# Power_Schematics.net
KiCad netlist of a schematic drawn in Altium Designer
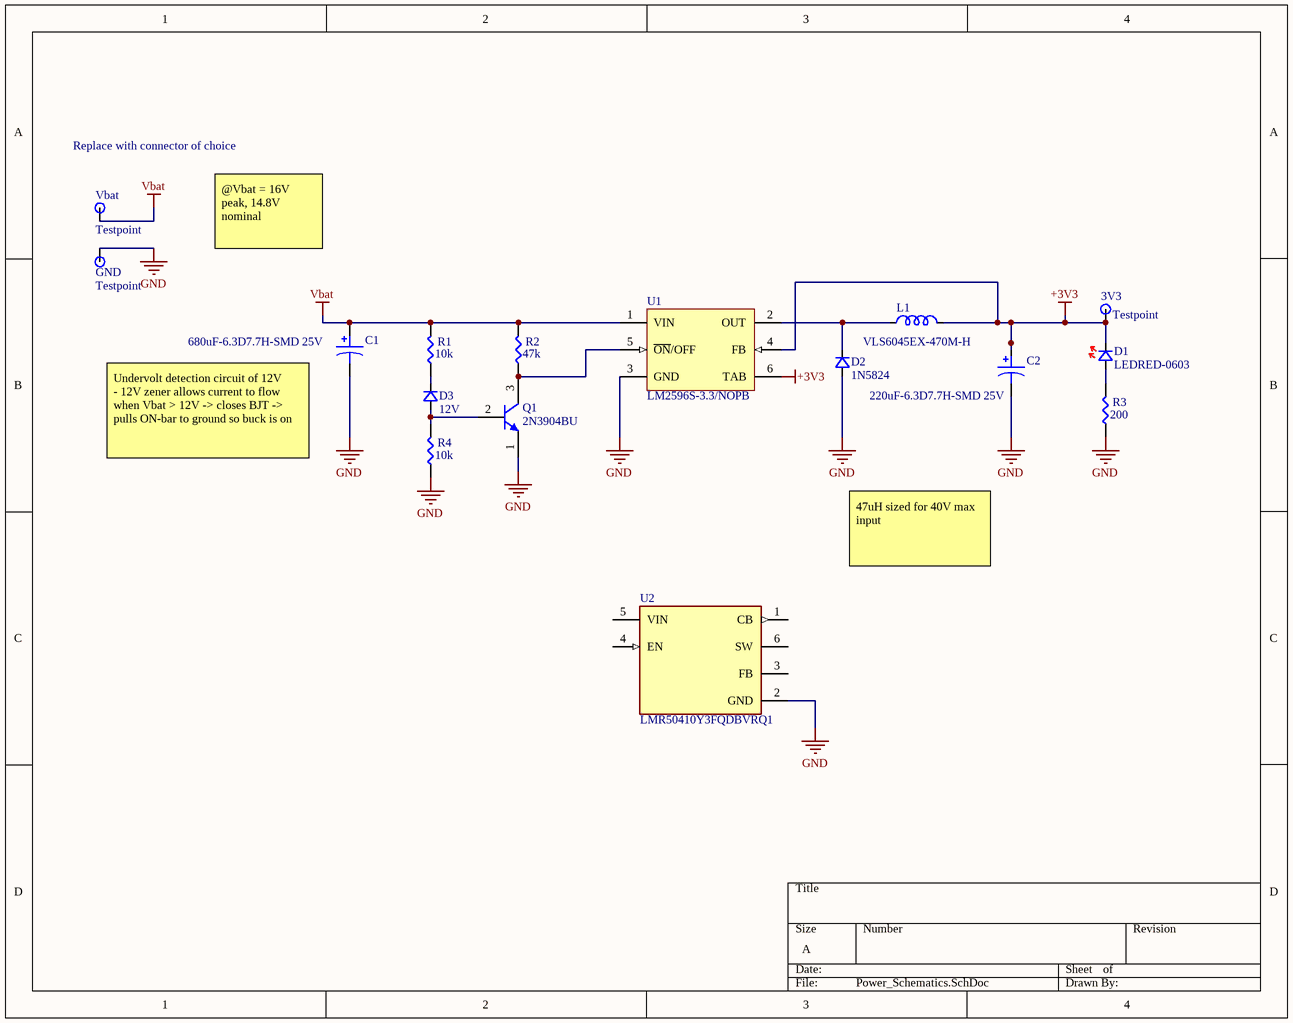
[diagram p0: Power_Schematics.SchDoc]

(export (version "E")
  (design (tool "Eeschema 10.0.6"))
  (components
    (comp (ref "3V3")
      (value "Testpoint")
      (footprint "Testpoint")
      (fields (field (name "SOURCE") "ife19_Elec_Library.SchLib"))
      (libsource (lib "Illini Formula Electric") (part "Testpoint"))
    )
    (comp (ref "C1")
      (value "680uF-6.3D7.7H-SMD 25V")
      (footprint "CAP-6.3D7.7H-SMD")
      (fields (field (name "SOURCE") "ife19_Elec_Library.SchLib"))
      (libsource (lib "Illini Formula Electric") (part "CAP-6.3D7.7H-SMD"))
    )
    (comp (ref "C2")
      (value "220uF-6.3D7.7H-SMD 25V")
      (footprint "CAP-6.3D7.7H-SMD")
      (fields (field (name "SOURCE") "ife19_Elec_Library.SchLib"))
      (libsource (lib "Illini Formula Electric") (part "CAP-6.3D7.7H-SMD"))
    )
    (comp (ref "D1")
      (value "LEDRED-0603")
      (footprint "LEDRED-0603")
      (fields (field (name "SOURCE") "ife19_Elec_Library.SchLib"))
      (libsource (lib "") (part "Symbol_3"))
    )
    (comp (ref "D2")
      (value "1N5824")
      (footprint "DO41-10")
      (fields (field (name "SOURCE") "ife19_Elec_Library.SchLib"))
      (libsource (lib "Illini Formula Electric") (part "DIODE-DO41-10"))
    )
    (comp (ref "D3")
      (value "12V")
      (footprint "SOD123")
      (fields (field (name "SOURCE") "ife19_Elec_Library.SchLib"))
      (libsource (lib "") (part "Symbol_2"))
    )
    (comp (ref "GND")
      (value "Testpoint")
      (footprint "Testpoint")
      (fields (field (name "SOURCE") "ife19_Elec_Library.SchLib"))
      (libsource (lib "Illini Formula Electric") (part "Testpoint"))
    )
    (comp (ref "L1")
      (value "VLS6045EX-470M-H")
      (footprint "IND-6045")
      (fields (field (name "SOURCE") "ife19_Elec_Library.SchLib"))
      (libsource (lib "") (part "Symbol_1"))
    )
    (comp (ref "Q1")
      (value "2N3904BU")
      (footprint "FAIR-TO-92")
      (description "NPN General-Purpose Amplifier, 40 V VCEO, 0.2 A, -55 to 150 degC, 2-Pin TO-92, RoHS, Bulk")
      (fields (field (name "MANUFACTURER") "FairchildSemiconductor"))
      (libsource (lib "Altium Content Vault") (part "NPN-E1B2C3-3"))
    )
    (comp (ref "R1")
      (value "10k")
      (footprint "RES-0603")
      (fields (field (name "SOURCE") "ife19_Elec_Library.SchLib"))
      (libsource (lib "Illini Formula Electric") (part "Symbol"))
    )
    (comp (ref "R2")
      (value "47k")
      (footprint "RES-0603")
      (fields (field (name "SOURCE") "ife19_Elec_Library.SchLib"))
      (libsource (lib "Illini Formula Electric") (part "Symbol"))
    )
    (comp (ref "R3")
      (value "200")
      (footprint "RES-0603")
      (fields (field (name "SOURCE") "ife19_Elec_Library.SchLib"))
      (libsource (lib "Illini Formula Electric") (part "Symbol"))
    )
    (comp (ref "R4")
      (value "10k")
      (footprint "RES-0603")
      (fields (field (name "SOURCE") "ife19_Elec_Library.SchLib"))
      (libsource (lib "Illini Formula Electric") (part "Symbol"))
    )
    (comp (ref "U1")
      (value "LM2596S-3.3/NOPB")
      (footprint "KTT0005B_M")
      (description "SIMPLE SWITCHER® Power Converter 150 KHz 3A Step-Down Voltage Regulator, 5-pin TO-263, Pb-Free")
      (fields (field (name "MANUFACTURER") "Texas Instruments"))
      (libsource (lib "Altium Content Vault") (part "PM-REG-LM2575HVS-12"))
    )
    (comp (ref "U2")
      (value "LMR50410Y3FQDBVRQ1")
      (footprint "FP-DBV0006A-IPC_B")
      (description "Switching Regulator, Current-mode, 1A, 2100kHz Switching Freq-Max, PDSO6")
      (libsource (lib "Illini Formula Electric") (part "12fa689474542d891f5712928b85702"))
    )
    (comp (ref "Vbat")
      (value "Testpoint")
      (footprint "Testpoint")
      (fields (field (name "SOURCE") "ife19_Elec_Library.SchLib"))
      (libsource (lib "Illini Formula Electric") (part "Testpoint"))
    )
  )
  (nets
    (net (code "1") (name "+3V3") (class "Default")
      (node (ref "3V3") (pin "1") (pinfunction "1_1") (pintype "passive"))
      (node (ref "C2") (pin "POS") (pinfunction "+_POS") (pintype "passive"))
      (node (ref "D1") (pin "K") (pinfunction "K_K") (pintype "passive"))
      (node (ref "L1") (pin "2") (pinfunction "2_2") (pintype "passive"))
      (node (ref "U1") (pin "4") (pinfunction "FB_4") (pintype "input"))
      (node (ref "U1") (pin "6") (pinfunction "TAB_6") (pintype "power_in"))
    )
    (net (code "2") (name "GND") (class "Default")
      (node (ref "C1") (pin "NEG") (pinfunction "-_NEG") (pintype "passive"))
      (node (ref "C2") (pin "NEG") (pinfunction "-_NEG") (pintype "passive"))
      (node (ref "D2") (pin "A") (pinfunction "A_A") (pintype "passive"))
      (node (ref "GND") (pin "1") (pinfunction "1_1") (pintype "passive"))
      (node (ref "Q1") (pin "1") (pinfunction "E_1") (pintype "passive"))
      (node (ref "R3") (pin "1") (pinfunction "1_1") (pintype "passive"))
      (node (ref "R4") (pin "1") (pinfunction "1_1") (pintype "passive"))
      (node (ref "U1") (pin "3") (pinfunction "GND_3") (pintype "power_in"))
      (node (ref "U2") (pin "2") (pinfunction "GND_2") (pintype "power_in"))
    )
    (net (code "3") (name "Net-(D1-PadA)") (class "Default")
      (node (ref "D1") (pin "A") (pinfunction "A_A") (pintype "passive"))
      (node (ref "R3") (pin "2") (pinfunction "2_2") (pintype "passive"))
    )
    (net (code "4") (name "Net-(D3-PadK)") (class "Default")
      (node (ref "D3") (pin "K") (pinfunction "K_K") (pintype "passive"))
      (node (ref "R1") (pin "1") (pinfunction "1_1") (pintype "passive"))
    )
    (net (code "5") (name "Net-(Q1-B)") (class "Default")
      (node (ref "D3") (pin "A") (pinfunction "A_A") (pintype "passive"))
      (node (ref "Q1") (pin "2") (pinfunction "B_2") (pintype "passive"))
      (node (ref "R4") (pin "2") (pinfunction "2_2") (pintype "passive"))
    )
    (net (code "6") (name "Net-(Q1-C)") (class "Default")
      (node (ref "Q1") (pin "3") (pinfunction "C_3") (pintype "passive"))
      (node (ref "R2") (pin "1") (pinfunction "1_1") (pintype "passive"))
      (node (ref "U1") (pin "5") (pinfunction "~{ON}/OFF_5") (pintype "input"))
    )
    (net (code "7") (name "Net-(U1-OUT)") (class "Default")
      (node (ref "D2") (pin "K") (pinfunction "K_K") (pintype "passive"))
      (node (ref "L1") (pin "1") (pinfunction "1_1") (pintype "passive"))
      (node (ref "U1") (pin "2") (pinfunction "OUT_2") (pintype "power_in"))
    )
    (net (code "8") (name "Vbat") (class "Default")
      (node (ref "C1") (pin "POS") (pinfunction "+_POS") (pintype "passive"))
      (node (ref "R1") (pin "2") (pinfunction "2_2") (pintype "passive"))
      (node (ref "R2") (pin "2") (pinfunction "2_2") (pintype "passive"))
      (node (ref "U1") (pin "1") (pinfunction "VIN_1") (pintype "power_in"))
      (node (ref "Vbat") (pin "1") (pinfunction "1_1") (pintype "passive"))
    )
    (net (code "9") (name "unconnected-(U2-CB-Pad1)") (class "Default")
      (node (ref "U2") (pin "1") (pinfunction "CB_1") (pintype "output"))
    )
    (net (code "10") (name "unconnected-(U2-EN-Pad4)") (class "Default")
      (node (ref "U2") (pin "4") (pinfunction "EN_4") (pintype "input"))
    )
    (net (code "11") (name "unconnected-(U2-FB-Pad3)") (class "Default")
      (node (ref "U2") (pin "3") (pinfunction "FB_3") (pintype "passive"))
    )
    (net (code "12") (name "unconnected-(U2-SW-Pad6)") (class "Default")
      (node (ref "U2") (pin "6") (pinfunction "SW_6") (pintype "power_in"))
    )
    (net (code "13") (name "unconnected-(U2-VIN-Pad5)") (class "Default")
      (node (ref "U2") (pin "5") (pinfunction "VIN_5") (pintype "power_in"))
    )
  )
)
